# trashotron-optical-neuron.net
KiCad netlist of a schematic drawn in EAGLE
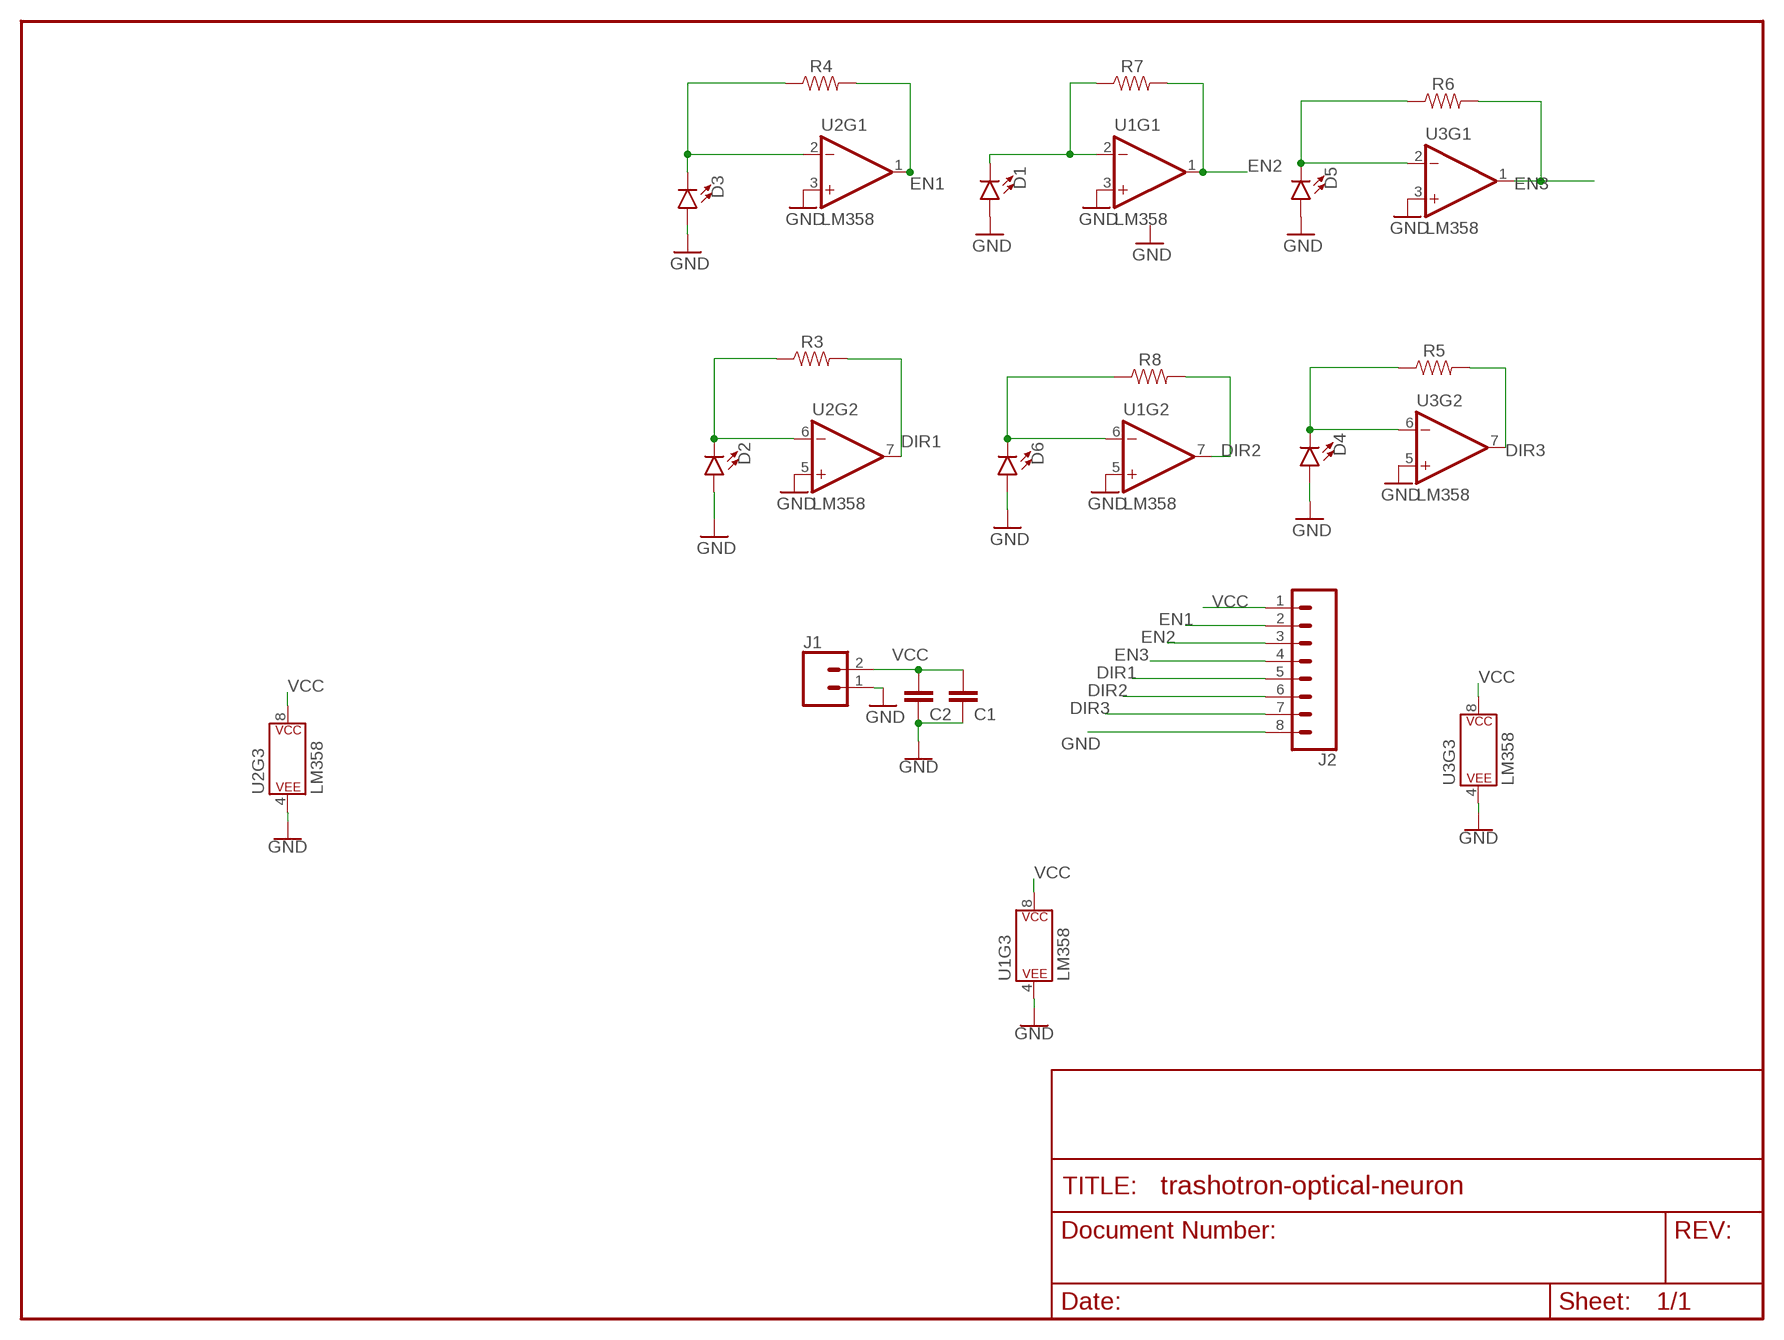
[diagram p0: schematic, sheet 1]

(export (version "E")
  (design (tool "Eeschema 10.0.6"))
  (components
    (comp (ref "C1")
      (value "C-EU050-050X075")
      (footprint "eagle-import:C050-050X075")
      (libsource (lib "eagle-import") (part "C-EU050-050X075"))
    )
    (comp (ref "C2")
      (value "C-EU050-050X075")
      (footprint "eagle-import:C050-050X075")
      (libsource (lib "eagle-import") (part "C-EU050-050X075"))
    )
    (comp (ref "D1")
      (value "LED3MM")
      (footprint "eagle-import:LED_3MM")
      (libsource (lib "eagle-import") (part "LED3MM"))
    )
    (comp (ref "D2")
      (value "LED3MM")
      (footprint "eagle-import:LED_3MM")
      (libsource (lib "eagle-import") (part "LED3MM"))
    )
    (comp (ref "D3")
      (value "LED3MM")
      (footprint "eagle-import:LED_3MM")
      (libsource (lib "eagle-import") (part "LED3MM"))
    )
    (comp (ref "D4")
      (value "LED3MM")
      (footprint "eagle-import:LED_3MM")
      (libsource (lib "eagle-import") (part "LED3MM"))
    )
    (comp (ref "D5")
      (value "LED3MM")
      (footprint "eagle-import:LED_3MM")
      (libsource (lib "eagle-import") (part "LED3MM"))
    )
    (comp (ref "D6")
      (value "LED3MM")
      (footprint "eagle-import:LED_3MM")
      (libsource (lib "eagle-import") (part "LED3MM"))
    )
    (comp (ref "J1")
      (value "CONN_02")
      (footprint "eagle-import:1X02")
      (libsource (lib "eagle-import") (part "CONN_02"))
    )
    (comp (ref "J2")
      (value "CONN_08\"")
      (footprint "eagle-import:1X08")
      (libsource (lib "eagle-import") (part "CONN_08{dblquote}"))
    )
    (comp (ref "R3")
      (value "RESISTORAXIAL-0.3")
      (footprint "eagle-import:AXIAL-0.3")
      (libsource (lib "eagle-import") (part "RESISTORAXIAL-0.3"))
    )
    (comp (ref "R4")
      (value "RESISTORAXIAL-0.3")
      (footprint "eagle-import:AXIAL-0.3")
      (libsource (lib "eagle-import") (part "RESISTORAXIAL-0.3"))
    )
    (comp (ref "R5")
      (value "RESISTORAXIAL-0.3")
      (footprint "eagle-import:AXIAL-0.3")
      (libsource (lib "eagle-import") (part "RESISTORAXIAL-0.3"))
    )
    (comp (ref "R6")
      (value "RESISTORAXIAL-0.3")
      (footprint "eagle-import:AXIAL-0.3")
      (libsource (lib "eagle-import") (part "RESISTORAXIAL-0.3"))
    )
    (comp (ref "R7")
      (value "RESISTORAXIAL-0.3")
      (footprint "eagle-import:AXIAL-0.3")
      (libsource (lib "eagle-import") (part "RESISTORAXIAL-0.3"))
    )
    (comp (ref "R8")
      (value "RESISTORAXIAL-0.3")
      (footprint "eagle-import:AXIAL-0.3")
      (libsource (lib "eagle-import") (part "RESISTORAXIAL-0.3"))
    )
    (comp (ref "U1")
      (value "LM358")
      (footprint "eagle-import:DIP08")
      (libsource (lib "eagle-import") (part "LM358"))
    )
    (comp (ref "U2")
      (value "LM358")
      (footprint "eagle-import:DIP08")
      (libsource (lib "eagle-import") (part "LM358"))
    )
    (comp (ref "U3")
      (value "LM358")
      (footprint "eagle-import:DIP08")
      (libsource (lib "eagle-import") (part "LM358"))
    )
  )
  (nets
    (net (code "1") (name "/DIR1") (class "Default")
      (node (ref "J2") (pin "5") (pinfunction "5_5") (pintype "passive"))
      (node (ref "R3") (pin "P$2") (pinfunction "2_P$2") (pintype "passive"))
      (node (ref "U2") (pin "7") (pinfunction "OUT_7") (pintype "output"))
    )
    (net (code "2") (name "/DIR2") (class "Default")
      (node (ref "J2") (pin "6") (pinfunction "6_6") (pintype "passive"))
      (node (ref "R8") (pin "P$2") (pinfunction "2_P$2") (pintype "passive"))
      (node (ref "U1") (pin "7") (pinfunction "OUT_7") (pintype "output"))
    )
    (net (code "3") (name "/DIR3") (class "Default")
      (node (ref "J2") (pin "7") (pinfunction "7_7") (pintype "passive"))
      (node (ref "R5") (pin "P$2") (pinfunction "2_P$2") (pintype "passive"))
      (node (ref "U3") (pin "7") (pinfunction "OUT_7") (pintype "output"))
    )
    (net (code "4") (name "/EN1") (class "Default")
      (node (ref "J2") (pin "2") (pinfunction "2_2") (pintype "passive"))
      (node (ref "R4") (pin "P$2") (pinfunction "2_P$2") (pintype "passive"))
      (node (ref "U2") (pin "1") (pinfunction "OUT_1") (pintype "output"))
    )
    (net (code "5") (name "/EN2") (class "Default")
      (node (ref "J2") (pin "3") (pinfunction "3_3") (pintype "passive"))
      (node (ref "R7") (pin "P$2") (pinfunction "2_P$2") (pintype "passive"))
      (node (ref "U1") (pin "1") (pinfunction "OUT_1") (pintype "output"))
    )
    (net (code "6") (name "/EN3") (class "Default")
      (node (ref "J2") (pin "4") (pinfunction "4_4") (pintype "passive"))
      (node (ref "R6") (pin "P$2") (pinfunction "2_P$2") (pintype "passive"))
      (node (ref "U3") (pin "1") (pinfunction "OUT_1") (pintype "output"))
    )
    (net (code "7") (name "/VCC") (class "Default")
      (node (ref "C1") (pin "2") (pinfunction "2_2") (pintype "passive"))
      (node (ref "C2") (pin "2") (pinfunction "2_2") (pintype "passive"))
      (node (ref "J1") (pin "2") (pinfunction "2_2") (pintype "passive"))
      (node (ref "J2") (pin "1") (pinfunction "1_1") (pintype "passive"))
      (node (ref "U1") (pin "8") (pinfunction "P$V+_8") (pintype "bidirectional"))
      (node (ref "U2") (pin "8") (pinfunction "P$V+_8") (pintype "bidirectional"))
      (node (ref "U3") (pin "8") (pinfunction "P$V+_8") (pintype "bidirectional"))
    )
    (net (code "8") (name "GND") (class "Default")
      (node (ref "C1") (pin "1") (pinfunction "1_1") (pintype "passive"))
      (node (ref "C2") (pin "1") (pinfunction "1_1") (pintype "passive"))
      (node (ref "D1") (pin "A") (pinfunction "A_A") (pintype "passive"))
      (node (ref "D2") (pin "A") (pinfunction "A_A") (pintype "passive"))
      (node (ref "D3") (pin "A") (pinfunction "A_A") (pintype "passive"))
      (node (ref "D4") (pin "A") (pinfunction "A_A") (pintype "passive"))
      (node (ref "D5") (pin "A") (pinfunction "A_A") (pintype "passive"))
      (node (ref "D6") (pin "A") (pinfunction "A_A") (pintype "passive"))
      (node (ref "J1") (pin "1") (pinfunction "1_1") (pintype "passive"))
      (node (ref "J2") (pin "8") (pinfunction "8_8") (pintype "passive"))
      (node (ref "U1") (pin "3") (pinfunction "+IN_3") (pintype "input"))
      (node (ref "U1") (pin "4") (pinfunction "P$V-_4") (pintype "bidirectional"))
      (node (ref "U1") (pin "5") (pinfunction "+IN_5") (pintype "input"))
      (node (ref "U2") (pin "3") (pinfunction "+IN_3") (pintype "input"))
      (node (ref "U2") (pin "4") (pinfunction "P$V-_4") (pintype "bidirectional"))
      (node (ref "U2") (pin "5") (pinfunction "+IN_5") (pintype "input"))
      (node (ref "U3") (pin "3") (pinfunction "+IN_3") (pintype "input"))
      (node (ref "U3") (pin "4") (pinfunction "P$V-_4") (pintype "bidirectional"))
      (node (ref "U3") (pin "5") (pinfunction "+IN_5") (pintype "input"))
    )
    (net (code "9") (name "Net-(D1-C)") (class "Default")
      (node (ref "D1") (pin "K") (pinfunction "C_K") (pintype "passive"))
      (node (ref "R7") (pin "P$1") (pinfunction "1_P$1") (pintype "passive"))
      (node (ref "U1") (pin "2") (pinfunction "-IN_2") (pintype "input"))
    )
    (net (code "10") (name "Net-(D2-C)") (class "Default")
      (node (ref "D2") (pin "K") (pinfunction "C_K") (pintype "passive"))
      (node (ref "R3") (pin "P$1") (pinfunction "1_P$1") (pintype "passive"))
      (node (ref "U2") (pin "6") (pinfunction "-IN_6") (pintype "input"))
    )
    (net (code "11") (name "Net-(D3-C)") (class "Default")
      (node (ref "D3") (pin "K") (pinfunction "C_K") (pintype "passive"))
      (node (ref "R4") (pin "P$1") (pinfunction "1_P$1") (pintype "passive"))
      (node (ref "U2") (pin "2") (pinfunction "-IN_2") (pintype "input"))
    )
    (net (code "12") (name "Net-(D4-C)") (class "Default")
      (node (ref "D4") (pin "K") (pinfunction "C_K") (pintype "passive"))
      (node (ref "R5") (pin "P$1") (pinfunction "1_P$1") (pintype "passive"))
      (node (ref "U3") (pin "6") (pinfunction "-IN_6") (pintype "input"))
    )
    (net (code "13") (name "Net-(D5-C)") (class "Default")
      (node (ref "D5") (pin "K") (pinfunction "C_K") (pintype "passive"))
      (node (ref "R6") (pin "P$1") (pinfunction "1_P$1") (pintype "passive"))
      (node (ref "U3") (pin "2") (pinfunction "-IN_2") (pintype "input"))
    )
    (net (code "14") (name "Net-(D6-C)") (class "Default")
      (node (ref "D6") (pin "K") (pinfunction "C_K") (pintype "passive"))
      (node (ref "R8") (pin "P$1") (pinfunction "1_P$1") (pintype "passive"))
      (node (ref "U1") (pin "6") (pinfunction "-IN_6") (pintype "input"))
    )
  )
)
